# chargetime_v1.net
KiCad netlist of a schematic drawn in EAGLE
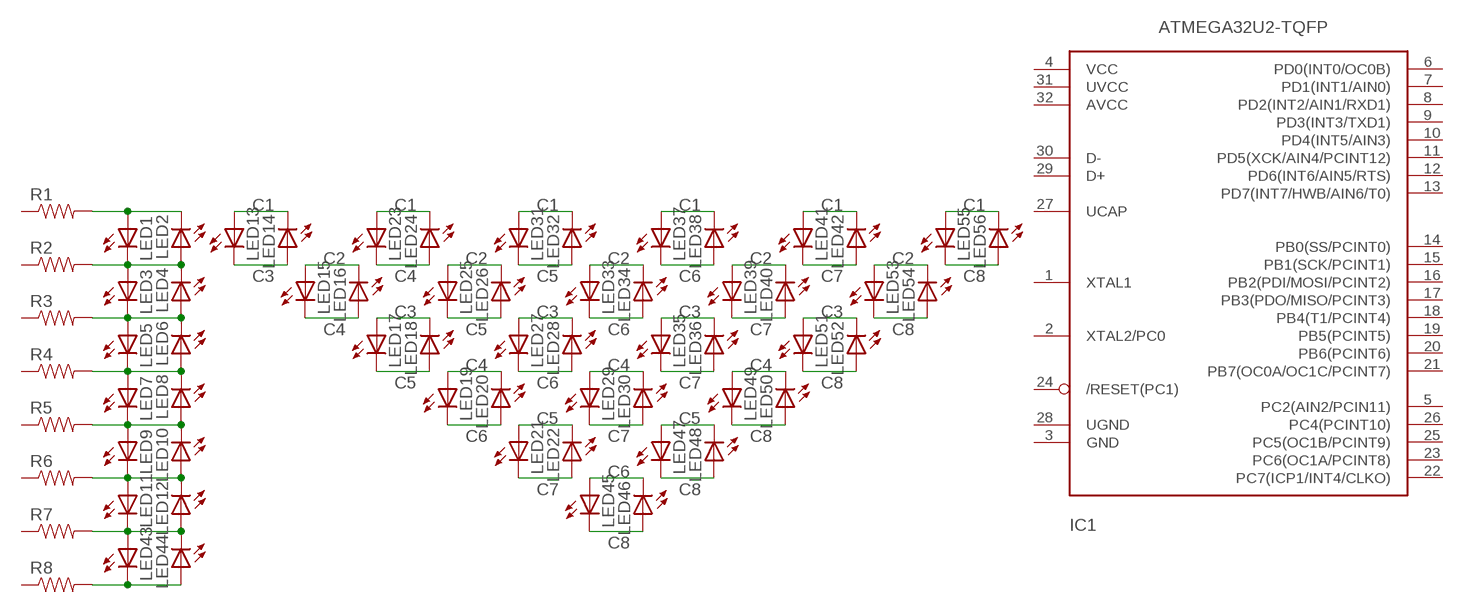
[diagram p0: schematic, sheet 1]

(export (version "E")
  (design (tool "Eeschema 10.0.6"))
  (components
    (comp (ref "IC1")
      (value "ATMEGA32U2-TQFP")
      (footprint "eagle-import:TQFP32-08")
      (libsource (lib "eagle-import") (part "ATMEGA32U2-TQFP"))
    )
    (comp (ref "LED1")
      (value "LEDCHIPLED_1206")
      (footprint "eagle-import:CHIPLED_1206")
      (libsource (lib "eagle-import") (part "LEDCHIPLED_1206"))
    )
    (comp (ref "LED2")
      (value "LEDCHIPLED_1206")
      (footprint "eagle-import:CHIPLED_1206")
      (libsource (lib "eagle-import") (part "LEDCHIPLED_1206"))
    )
    (comp (ref "LED3")
      (value "LEDCHIPLED_1206")
      (footprint "eagle-import:CHIPLED_1206")
      (libsource (lib "eagle-import") (part "LEDCHIPLED_1206"))
    )
    (comp (ref "LED4")
      (value "LEDCHIPLED_1206")
      (footprint "eagle-import:CHIPLED_1206")
      (libsource (lib "eagle-import") (part "LEDCHIPLED_1206"))
    )
    (comp (ref "LED5")
      (value "LEDCHIPLED_1206")
      (footprint "eagle-import:CHIPLED_1206")
      (libsource (lib "eagle-import") (part "LEDCHIPLED_1206"))
    )
    (comp (ref "LED6")
      (value "LEDCHIPLED_1206")
      (footprint "eagle-import:CHIPLED_1206")
      (libsource (lib "eagle-import") (part "LEDCHIPLED_1206"))
    )
    (comp (ref "LED7")
      (value "LEDCHIPLED_1206")
      (footprint "eagle-import:CHIPLED_1206")
      (libsource (lib "eagle-import") (part "LEDCHIPLED_1206"))
    )
    (comp (ref "LED8")
      (value "LEDCHIPLED_1206")
      (footprint "eagle-import:CHIPLED_1206")
      (libsource (lib "eagle-import") (part "LEDCHIPLED_1206"))
    )
    (comp (ref "LED9")
      (value "LEDCHIPLED_1206")
      (footprint "eagle-import:CHIPLED_1206")
      (libsource (lib "eagle-import") (part "LEDCHIPLED_1206"))
    )
    (comp (ref "LED10")
      (value "LEDCHIPLED_1206")
      (footprint "eagle-import:CHIPLED_1206")
      (libsource (lib "eagle-import") (part "LEDCHIPLED_1206"))
    )
    (comp (ref "LED11")
      (value "LEDCHIPLED_1206")
      (footprint "eagle-import:CHIPLED_1206")
      (libsource (lib "eagle-import") (part "LEDCHIPLED_1206"))
    )
    (comp (ref "LED12")
      (value "LEDCHIPLED_1206")
      (footprint "eagle-import:CHIPLED_1206")
      (libsource (lib "eagle-import") (part "LEDCHIPLED_1206"))
    )
    (comp (ref "LED13")
      (value "LEDCHIPLED_1206")
      (footprint "eagle-import:CHIPLED_1206")
      (libsource (lib "eagle-import") (part "LEDCHIPLED_1206"))
    )
    (comp (ref "LED14")
      (value "LEDCHIPLED_1206")
      (footprint "eagle-import:CHIPLED_1206")
      (libsource (lib "eagle-import") (part "LEDCHIPLED_1206"))
    )
    (comp (ref "LED15")
      (value "LEDCHIPLED_1206")
      (footprint "eagle-import:CHIPLED_1206")
      (libsource (lib "eagle-import") (part "LEDCHIPLED_1206"))
    )
    (comp (ref "LED16")
      (value "LEDCHIPLED_1206")
      (footprint "eagle-import:CHIPLED_1206")
      (libsource (lib "eagle-import") (part "LEDCHIPLED_1206"))
    )
    (comp (ref "LED17")
      (value "LEDCHIPLED_1206")
      (footprint "eagle-import:CHIPLED_1206")
      (libsource (lib "eagle-import") (part "LEDCHIPLED_1206"))
    )
    (comp (ref "LED18")
      (value "LEDCHIPLED_1206")
      (footprint "eagle-import:CHIPLED_1206")
      (libsource (lib "eagle-import") (part "LEDCHIPLED_1206"))
    )
    (comp (ref "LED19")
      (value "LEDCHIPLED_1206")
      (footprint "eagle-import:CHIPLED_1206")
      (libsource (lib "eagle-import") (part "LEDCHIPLED_1206"))
    )
    (comp (ref "LED20")
      (value "LEDCHIPLED_1206")
      (footprint "eagle-import:CHIPLED_1206")
      (libsource (lib "eagle-import") (part "LEDCHIPLED_1206"))
    )
    (comp (ref "LED21")
      (value "LEDCHIPLED_1206")
      (footprint "eagle-import:CHIPLED_1206")
      (libsource (lib "eagle-import") (part "LEDCHIPLED_1206"))
    )
    (comp (ref "LED22")
      (value "LEDCHIPLED_1206")
      (footprint "eagle-import:CHIPLED_1206")
      (libsource (lib "eagle-import") (part "LEDCHIPLED_1206"))
    )
    (comp (ref "LED23")
      (value "LEDCHIPLED_1206")
      (footprint "eagle-import:CHIPLED_1206")
      (libsource (lib "eagle-import") (part "LEDCHIPLED_1206"))
    )
    (comp (ref "LED24")
      (value "LEDCHIPLED_1206")
      (footprint "eagle-import:CHIPLED_1206")
      (libsource (lib "eagle-import") (part "LEDCHIPLED_1206"))
    )
    (comp (ref "LED25")
      (value "LEDCHIPLED_1206")
      (footprint "eagle-import:CHIPLED_1206")
      (libsource (lib "eagle-import") (part "LEDCHIPLED_1206"))
    )
    (comp (ref "LED26")
      (value "LEDCHIPLED_1206")
      (footprint "eagle-import:CHIPLED_1206")
      (libsource (lib "eagle-import") (part "LEDCHIPLED_1206"))
    )
    (comp (ref "LED27")
      (value "LEDCHIPLED_1206")
      (footprint "eagle-import:CHIPLED_1206")
      (libsource (lib "eagle-import") (part "LEDCHIPLED_1206"))
    )
    (comp (ref "LED28")
      (value "LEDCHIPLED_1206")
      (footprint "eagle-import:CHIPLED_1206")
      (libsource (lib "eagle-import") (part "LEDCHIPLED_1206"))
    )
    (comp (ref "LED29")
      (value "LEDCHIPLED_1206")
      (footprint "eagle-import:CHIPLED_1206")
      (libsource (lib "eagle-import") (part "LEDCHIPLED_1206"))
    )
    (comp (ref "LED30")
      (value "LEDCHIPLED_1206")
      (footprint "eagle-import:CHIPLED_1206")
      (libsource (lib "eagle-import") (part "LEDCHIPLED_1206"))
    )
    (comp (ref "LED31")
      (value "LEDCHIPLED_1206")
      (footprint "eagle-import:CHIPLED_1206")
      (libsource (lib "eagle-import") (part "LEDCHIPLED_1206"))
    )
    (comp (ref "LED32")
      (value "LEDCHIPLED_1206")
      (footprint "eagle-import:CHIPLED_1206")
      (libsource (lib "eagle-import") (part "LEDCHIPLED_1206"))
    )
    (comp (ref "LED33")
      (value "LEDCHIPLED_1206")
      (footprint "eagle-import:CHIPLED_1206")
      (libsource (lib "eagle-import") (part "LEDCHIPLED_1206"))
    )
    (comp (ref "LED34")
      (value "LEDCHIPLED_1206")
      (footprint "eagle-import:CHIPLED_1206")
      (libsource (lib "eagle-import") (part "LEDCHIPLED_1206"))
    )
    (comp (ref "LED35")
      (value "LEDCHIPLED_1206")
      (footprint "eagle-import:CHIPLED_1206")
      (libsource (lib "eagle-import") (part "LEDCHIPLED_1206"))
    )
    (comp (ref "LED36")
      (value "LEDCHIPLED_1206")
      (footprint "eagle-import:CHIPLED_1206")
      (libsource (lib "eagle-import") (part "LEDCHIPLED_1206"))
    )
    (comp (ref "LED37")
      (value "LEDCHIPLED_1206")
      (footprint "eagle-import:CHIPLED_1206")
      (libsource (lib "eagle-import") (part "LEDCHIPLED_1206"))
    )
    (comp (ref "LED38")
      (value "LEDCHIPLED_1206")
      (footprint "eagle-import:CHIPLED_1206")
      (libsource (lib "eagle-import") (part "LEDCHIPLED_1206"))
    )
    (comp (ref "LED39")
      (value "LEDCHIPLED_1206")
      (footprint "eagle-import:CHIPLED_1206")
      (libsource (lib "eagle-import") (part "LEDCHIPLED_1206"))
    )
    (comp (ref "LED40")
      (value "LEDCHIPLED_1206")
      (footprint "eagle-import:CHIPLED_1206")
      (libsource (lib "eagle-import") (part "LEDCHIPLED_1206"))
    )
    (comp (ref "LED41")
      (value "LEDCHIPLED_1206")
      (footprint "eagle-import:CHIPLED_1206")
      (libsource (lib "eagle-import") (part "LEDCHIPLED_1206"))
    )
    (comp (ref "LED42")
      (value "LEDCHIPLED_1206")
      (footprint "eagle-import:CHIPLED_1206")
      (libsource (lib "eagle-import") (part "LEDCHIPLED_1206"))
    )
    (comp (ref "LED43")
      (value "LEDCHIPLED_1206")
      (footprint "eagle-import:CHIPLED_1206")
      (libsource (lib "eagle-import") (part "LEDCHIPLED_1206"))
    )
    (comp (ref "LED44")
      (value "LEDCHIPLED_1206")
      (footprint "eagle-import:CHIPLED_1206")
      (libsource (lib "eagle-import") (part "LEDCHIPLED_1206"))
    )
    (comp (ref "LED45")
      (value "LEDCHIPLED_1206")
      (footprint "eagle-import:CHIPLED_1206")
      (libsource (lib "eagle-import") (part "LEDCHIPLED_1206"))
    )
    (comp (ref "LED46")
      (value "LEDCHIPLED_1206")
      (footprint "eagle-import:CHIPLED_1206")
      (libsource (lib "eagle-import") (part "LEDCHIPLED_1206"))
    )
    (comp (ref "LED47")
      (value "LEDCHIPLED_1206")
      (footprint "eagle-import:CHIPLED_1206")
      (libsource (lib "eagle-import") (part "LEDCHIPLED_1206"))
    )
    (comp (ref "LED48")
      (value "LEDCHIPLED_1206")
      (footprint "eagle-import:CHIPLED_1206")
      (libsource (lib "eagle-import") (part "LEDCHIPLED_1206"))
    )
    (comp (ref "LED49")
      (value "LEDCHIPLED_1206")
      (footprint "eagle-import:CHIPLED_1206")
      (libsource (lib "eagle-import") (part "LEDCHIPLED_1206"))
    )
    (comp (ref "LED50")
      (value "LEDCHIPLED_1206")
      (footprint "eagle-import:CHIPLED_1206")
      (libsource (lib "eagle-import") (part "LEDCHIPLED_1206"))
    )
    (comp (ref "LED51")
      (value "LEDCHIPLED_1206")
      (footprint "eagle-import:CHIPLED_1206")
      (libsource (lib "eagle-import") (part "LEDCHIPLED_1206"))
    )
    (comp (ref "LED52")
      (value "LEDCHIPLED_1206")
      (footprint "eagle-import:CHIPLED_1206")
      (libsource (lib "eagle-import") (part "LEDCHIPLED_1206"))
    )
    (comp (ref "LED53")
      (value "LEDCHIPLED_1206")
      (footprint "eagle-import:CHIPLED_1206")
      (libsource (lib "eagle-import") (part "LEDCHIPLED_1206"))
    )
    (comp (ref "LED54")
      (value "LEDCHIPLED_1206")
      (footprint "eagle-import:CHIPLED_1206")
      (libsource (lib "eagle-import") (part "LEDCHIPLED_1206"))
    )
    (comp (ref "LED55")
      (value "LEDCHIPLED_1206")
      (footprint "eagle-import:CHIPLED_1206")
      (libsource (lib "eagle-import") (part "LEDCHIPLED_1206"))
    )
    (comp (ref "LED56")
      (value "LEDCHIPLED_1206")
      (footprint "eagle-import:CHIPLED_1206")
      (libsource (lib "eagle-import") (part "LEDCHIPLED_1206"))
    )
    (comp (ref "R1")
      (value "RESISTOR1206")
      (footprint "eagle-import:1206")
      (libsource (lib "eagle-import") (part "RESISTOR1206"))
    )
    (comp (ref "R2")
      (value "RESISTOR1206")
      (footprint "eagle-import:1206")
      (libsource (lib "eagle-import") (part "RESISTOR1206"))
    )
    (comp (ref "R3")
      (value "RESISTOR1206")
      (footprint "eagle-import:1206")
      (libsource (lib "eagle-import") (part "RESISTOR1206"))
    )
    (comp (ref "R4")
      (value "RESISTOR1206")
      (footprint "eagle-import:1206")
      (libsource (lib "eagle-import") (part "RESISTOR1206"))
    )
    (comp (ref "R5")
      (value "RESISTOR1206")
      (footprint "eagle-import:1206")
      (libsource (lib "eagle-import") (part "RESISTOR1206"))
    )
    (comp (ref "R6")
      (value "RESISTOR1206")
      (footprint "eagle-import:1206")
      (libsource (lib "eagle-import") (part "RESISTOR1206"))
    )
    (comp (ref "R7")
      (value "RESISTOR1206")
      (footprint "eagle-import:1206")
      (libsource (lib "eagle-import") (part "RESISTOR1206"))
    )
    (comp (ref "R8")
      (value "RESISTOR1206")
      (footprint "eagle-import:1206")
      (libsource (lib "eagle-import") (part "RESISTOR1206"))
    )
  )
  (nets
    (net (code "1") (name "/C1") (class "Default")
      (node (ref "LED1") (pin "A") (pinfunction "A_A") (pintype "passive"))
      (node (ref "LED13") (pin "A") (pinfunction "A_A") (pintype "passive"))
      (node (ref "LED14") (pin "C") (pinfunction "C_C") (pintype "passive"))
      (node (ref "LED2") (pin "C") (pinfunction "C_C") (pintype "passive"))
      (node (ref "LED23") (pin "A") (pinfunction "A_A") (pintype "passive"))
      (node (ref "LED24") (pin "C") (pinfunction "C_C") (pintype "passive"))
      (node (ref "LED31") (pin "A") (pinfunction "A_A") (pintype "passive"))
      (node (ref "LED32") (pin "C") (pinfunction "C_C") (pintype "passive"))
      (node (ref "LED37") (pin "A") (pinfunction "A_A") (pintype "passive"))
      (node (ref "LED38") (pin "C") (pinfunction "C_C") (pintype "passive"))
      (node (ref "LED41") (pin "A") (pinfunction "A_A") (pintype "passive"))
      (node (ref "LED42") (pin "C") (pinfunction "C_C") (pintype "passive"))
      (node (ref "LED55") (pin "A") (pinfunction "A_A") (pintype "passive"))
      (node (ref "LED56") (pin "C") (pinfunction "C_C") (pintype "passive"))
      (node (ref "R1") (pin "2") (pinfunction "2_2") (pintype "passive"))
    )
    (net (code "2") (name "/C2") (class "Default")
      (node (ref "LED1") (pin "C") (pinfunction "C_C") (pintype "passive"))
      (node (ref "LED15") (pin "A") (pinfunction "A_A") (pintype "passive"))
      (node (ref "LED16") (pin "C") (pinfunction "C_C") (pintype "passive"))
      (node (ref "LED2") (pin "A") (pinfunction "A_A") (pintype "passive"))
      (node (ref "LED25") (pin "A") (pinfunction "A_A") (pintype "passive"))
      (node (ref "LED26") (pin "C") (pinfunction "C_C") (pintype "passive"))
      (node (ref "LED3") (pin "A") (pinfunction "A_A") (pintype "passive"))
      (node (ref "LED33") (pin "A") (pinfunction "A_A") (pintype "passive"))
      (node (ref "LED34") (pin "C") (pinfunction "C_C") (pintype "passive"))
      (node (ref "LED39") (pin "A") (pinfunction "A_A") (pintype "passive"))
      (node (ref "LED4") (pin "C") (pinfunction "C_C") (pintype "passive"))
      (node (ref "LED40") (pin "C") (pinfunction "C_C") (pintype "passive"))
      (node (ref "LED53") (pin "A") (pinfunction "A_A") (pintype "passive"))
      (node (ref "LED54") (pin "C") (pinfunction "C_C") (pintype "passive"))
      (node (ref "R2") (pin "2") (pinfunction "2_2") (pintype "passive"))
    )
    (net (code "3") (name "/C3") (class "Default")
      (node (ref "LED13") (pin "C") (pinfunction "C_C") (pintype "passive"))
      (node (ref "LED14") (pin "A") (pinfunction "A_A") (pintype "passive"))
      (node (ref "LED17") (pin "A") (pinfunction "A_A") (pintype "passive"))
      (node (ref "LED18") (pin "C") (pinfunction "C_C") (pintype "passive"))
      (node (ref "LED27") (pin "A") (pinfunction "A_A") (pintype "passive"))
      (node (ref "LED28") (pin "C") (pinfunction "C_C") (pintype "passive"))
      (node (ref "LED3") (pin "C") (pinfunction "C_C") (pintype "passive"))
      (node (ref "LED35") (pin "A") (pinfunction "A_A") (pintype "passive"))
      (node (ref "LED36") (pin "C") (pinfunction "C_C") (pintype "passive"))
      (node (ref "LED4") (pin "A") (pinfunction "A_A") (pintype "passive"))
      (node (ref "LED5") (pin "A") (pinfunction "A_A") (pintype "passive"))
      (node (ref "LED51") (pin "A") (pinfunction "A_A") (pintype "passive"))
      (node (ref "LED52") (pin "C") (pinfunction "C_C") (pintype "passive"))
      (node (ref "LED6") (pin "C") (pinfunction "C_C") (pintype "passive"))
      (node (ref "R3") (pin "2") (pinfunction "2_2") (pintype "passive"))
    )
    (net (code "4") (name "/C4") (class "Default")
      (node (ref "LED15") (pin "C") (pinfunction "C_C") (pintype "passive"))
      (node (ref "LED16") (pin "A") (pinfunction "A_A") (pintype "passive"))
      (node (ref "LED19") (pin "A") (pinfunction "A_A") (pintype "passive"))
      (node (ref "LED20") (pin "C") (pinfunction "C_C") (pintype "passive"))
      (node (ref "LED23") (pin "C") (pinfunction "C_C") (pintype "passive"))
      (node (ref "LED24") (pin "A") (pinfunction "A_A") (pintype "passive"))
      (node (ref "LED29") (pin "A") (pinfunction "A_A") (pintype "passive"))
      (node (ref "LED30") (pin "C") (pinfunction "C_C") (pintype "passive"))
      (node (ref "LED49") (pin "A") (pinfunction "A_A") (pintype "passive"))
      (node (ref "LED5") (pin "C") (pinfunction "C_C") (pintype "passive"))
      (node (ref "LED50") (pin "C") (pinfunction "C_C") (pintype "passive"))
      (node (ref "LED6") (pin "A") (pinfunction "A_A") (pintype "passive"))
      (node (ref "LED7") (pin "A") (pinfunction "A_A") (pintype "passive"))
      (node (ref "LED8") (pin "C") (pinfunction "C_C") (pintype "passive"))
      (node (ref "R4") (pin "2") (pinfunction "2_2") (pintype "passive"))
    )
    (net (code "5") (name "/C5") (class "Default")
      (node (ref "LED10") (pin "C") (pinfunction "C_C") (pintype "passive"))
      (node (ref "LED17") (pin "C") (pinfunction "C_C") (pintype "passive"))
      (node (ref "LED18") (pin "A") (pinfunction "A_A") (pintype "passive"))
      (node (ref "LED21") (pin "A") (pinfunction "A_A") (pintype "passive"))
      (node (ref "LED22") (pin "C") (pinfunction "C_C") (pintype "passive"))
      (node (ref "LED25") (pin "C") (pinfunction "C_C") (pintype "passive"))
      (node (ref "LED26") (pin "A") (pinfunction "A_A") (pintype "passive"))
      (node (ref "LED31") (pin "C") (pinfunction "C_C") (pintype "passive"))
      (node (ref "LED32") (pin "A") (pinfunction "A_A") (pintype "passive"))
      (node (ref "LED47") (pin "A") (pinfunction "A_A") (pintype "passive"))
      (node (ref "LED48") (pin "C") (pinfunction "C_C") (pintype "passive"))
      (node (ref "LED7") (pin "C") (pinfunction "C_C") (pintype "passive"))
      (node (ref "LED8") (pin "A") (pinfunction "A_A") (pintype "passive"))
      (node (ref "LED9") (pin "A") (pinfunction "A_A") (pintype "passive"))
      (node (ref "R5") (pin "2") (pinfunction "2_2") (pintype "passive"))
    )
    (net (code "6") (name "/C6") (class "Default")
      (node (ref "LED10") (pin "A") (pinfunction "A_A") (pintype "passive"))
      (node (ref "LED11") (pin "A") (pinfunction "A_A") (pintype "passive"))
      (node (ref "LED12") (pin "C") (pinfunction "C_C") (pintype "passive"))
      (node (ref "LED19") (pin "C") (pinfunction "C_C") (pintype "passive"))
      (node (ref "LED20") (pin "A") (pinfunction "A_A") (pintype "passive"))
      (node (ref "LED27") (pin "C") (pinfunction "C_C") (pintype "passive"))
      (node (ref "LED28") (pin "A") (pinfunction "A_A") (pintype "passive"))
      (node (ref "LED33") (pin "C") (pinfunction "C_C") (pintype "passive"))
      (node (ref "LED34") (pin "A") (pinfunction "A_A") (pintype "passive"))
      (node (ref "LED37") (pin "C") (pinfunction "C_C") (pintype "passive"))
      (node (ref "LED38") (pin "A") (pinfunction "A_A") (pintype "passive"))
      (node (ref "LED45") (pin "A") (pinfunction "A_A") (pintype "passive"))
      (node (ref "LED46") (pin "C") (pinfunction "C_C") (pintype "passive"))
      (node (ref "LED9") (pin "C") (pinfunction "C_C") (pintype "passive"))
      (node (ref "R6") (pin "2") (pinfunction "2_2") (pintype "passive"))
    )
    (net (code "7") (name "/C7") (class "Default")
      (node (ref "LED11") (pin "C") (pinfunction "C_C") (pintype "passive"))
      (node (ref "LED12") (pin "A") (pinfunction "A_A") (pintype "passive"))
      (node (ref "LED21") (pin "C") (pinfunction "C_C") (pintype "passive"))
      (node (ref "LED22") (pin "A") (pinfunction "A_A") (pintype "passive"))
      (node (ref "LED29") (pin "C") (pinfunction "C_C") (pintype "passive"))
      (node (ref "LED30") (pin "A") (pinfunction "A_A") (pintype "passive"))
      (node (ref "LED35") (pin "C") (pinfunction "C_C") (pintype "passive"))
      (node (ref "LED36") (pin "A") (pinfunction "A_A") (pintype "passive"))
      (node (ref "LED39") (pin "C") (pinfunction "C_C") (pintype "passive"))
      (node (ref "LED40") (pin "A") (pinfunction "A_A") (pintype "passive"))
      (node (ref "LED41") (pin "C") (pinfunction "C_C") (pintype "passive"))
      (node (ref "LED42") (pin "A") (pinfunction "A_A") (pintype "passive"))
      (node (ref "LED43") (pin "A") (pinfunction "A_A") (pintype "passive"))
      (node (ref "LED44") (pin "C") (pinfunction "C_C") (pintype "passive"))
      (node (ref "R7") (pin "2") (pinfunction "2_2") (pintype "passive"))
    )
    (net (code "8") (name "/C8") (class "Default")
      (node (ref "LED43") (pin "C") (pinfunction "C_C") (pintype "passive"))
      (node (ref "LED44") (pin "A") (pinfunction "A_A") (pintype "passive"))
      (node (ref "LED45") (pin "C") (pinfunction "C_C") (pintype "passive"))
      (node (ref "LED46") (pin "A") (pinfunction "A_A") (pintype "passive"))
      (node (ref "LED47") (pin "C") (pinfunction "C_C") (pintype "passive"))
      (node (ref "LED48") (pin "A") (pinfunction "A_A") (pintype "passive"))
      (node (ref "LED49") (pin "C") (pinfunction "C_C") (pintype "passive"))
      (node (ref "LED50") (pin "A") (pinfunction "A_A") (pintype "passive"))
      (node (ref "LED51") (pin "C") (pinfunction "C_C") (pintype "passive"))
      (node (ref "LED52") (pin "A") (pinfunction "A_A") (pintype "passive"))
      (node (ref "LED53") (pin "C") (pinfunction "C_C") (pintype "passive"))
      (node (ref "LED54") (pin "A") (pinfunction "A_A") (pintype "passive"))
      (node (ref "LED55") (pin "C") (pinfunction "C_C") (pintype "passive"))
      (node (ref "LED56") (pin "A") (pinfunction "A_A") (pintype "passive"))
      (node (ref "R8") (pin "2") (pinfunction "2_2") (pintype "passive"))
    )
    (net (code "9") (name "unconnected-(IC1-AVCC-Pad32)") (class "Default")
      (node (ref "IC1") (pin "32") (pinfunction "AVCC_32") (pintype "bidirectional"))
    )
    (net (code "10") (name "unconnected-(IC1-D+-Pad29)") (class "Default")
      (node (ref "IC1") (pin "29") (pinfunction "D+_29") (pintype "bidirectional"))
    )
    (net (code "11") (name "unconnected-(IC1-D--Pad30)") (class "Default")
      (node (ref "IC1") (pin "30") (pinfunction "D-_30") (pintype "bidirectional"))
    )
    (net (code "12") (name "unconnected-(IC1-GND-Pad3)") (class "Default")
      (node (ref "IC1") (pin "3") (pinfunction "GND_3") (pintype "bidirectional"))
    )
    (net (code "13") (name "unconnected-(IC1-PB0(SS{slash}PCINT0)-Pad14)") (class "Default")
      (node (ref "IC1") (pin "14") (pinfunction "PB0(SS/PCINT0)_14") (pintype "bidirectional"))
    )
    (net (code "14") (name "unconnected-(IC1-PB1(SCK{slash}PCINT1)-Pad15)") (class "Default")
      (node (ref "IC1") (pin "15") (pinfunction "PB1(SCK/PCINT1)_15") (pintype "bidirectional"))
    )
    (net (code "15") (name "unconnected-(IC1-PB2(PDI{slash}MOSI{slash}PCINT2)-Pad16)") (class "Default")
      (node (ref "IC1") (pin "16") (pinfunction "PB2(PDI/MOSI/PCINT2)_16") (pintype "bidirectional"))
    )
    (net (code "16") (name "unconnected-(IC1-PB3(PDO{slash}MISO{slash}PCINT3)-Pad17)") (class "Default")
      (node (ref "IC1") (pin "17") (pinfunction "PB3(PDO/MISO/PCINT3)_17") (pintype "bidirectional"))
    )
    (net (code "17") (name "unconnected-(IC1-PB4(T1{slash}PCINT4)-Pad18)") (class "Default")
      (node (ref "IC1") (pin "18") (pinfunction "PB4(T1/PCINT4)_18") (pintype "bidirectional"))
    )
    (net (code "18") (name "unconnected-(IC1-PB5(PCINT5)-Pad19)") (class "Default")
      (node (ref "IC1") (pin "19") (pinfunction "PB5(PCINT5)_19") (pintype "bidirectional"))
    )
    (net (code "19") (name "unconnected-(IC1-PB6(PCINT6)-Pad20)") (class "Default")
      (node (ref "IC1") (pin "20") (pinfunction "PB6(PCINT6)_20") (pintype "bidirectional"))
    )
    (net (code "20") (name "unconnected-(IC1-PB7(OC0A{slash}OC1C{slash}PCINT7)-Pad21)") (class "Default")
      (node (ref "IC1") (pin "21") (pinfunction "PB7(OC0A/OC1C/PCINT7)_21") (pintype "bidirectional"))
    )
    (net (code "21") (name "unconnected-(IC1-PC2(AIN2{slash}PCIN11)-Pad5)") (class "Default")
      (node (ref "IC1") (pin "5") (pinfunction "PC2(AIN2/PCIN11)_5") (pintype "bidirectional"))
    )
    (net (code "22") (name "unconnected-(IC1-PC4(PCINT10)-Pad26)") (class "Default")
      (node (ref "IC1") (pin "26") (pinfunction "PC4(PCINT10)_26") (pintype "bidirectional"))
    )
    (net (code "23") (name "unconnected-(IC1-PC5(OC1B{slash}PCINT9)-Pad25)") (class "Default")
      (node (ref "IC1") (pin "25") (pinfunction "PC5(OC1B/PCINT9)_25") (pintype "bidirectional"))
    )
    (net (code "24") (name "unconnected-(IC1-PC6(OC1A{slash}PCINT8)-Pad23)") (class "Default")
      (node (ref "IC1") (pin "23") (pinfunction "PC6(OC1A/PCINT8)_23") (pintype "bidirectional"))
    )
    (net (code "25") (name "unconnected-(IC1-PC7(ICP1{slash}INT4{slash}CLKO)-Pad22)") (class "Default")
      (node (ref "IC1") (pin "22") (pinfunction "PC7(ICP1/INT4/CLKO)_22") (pintype "bidirectional"))
    )
    (net (code "26") (name "unconnected-(IC1-PD0(INT0{slash}OC0B)-Pad6)") (class "Default")
      (node (ref "IC1") (pin "6") (pinfunction "PD0(INT0/OC0B)_6") (pintype "bidirectional"))
    )
    (net (code "27") (name "unconnected-(IC1-PD1(INT1{slash}AIN0)-Pad7)") (class "Default")
      (node (ref "IC1") (pin "7") (pinfunction "PD1(INT1/AIN0)_7") (pintype "bidirectional"))
    )
    (net (code "28") (name "unconnected-(IC1-PD2(INT2{slash}AIN1{slash}RXD1)-Pad8)") (class "Default")
      (node (ref "IC1") (pin "8") (pinfunction "PD2(INT2/AIN1/RXD1)_8") (pintype "bidirectional"))
    )
    (net (code "29") (name "unconnected-(IC1-PD3(INT3{slash}TXD1)-Pad9)") (class "Default")
      (node (ref "IC1") (pin "9") (pinfunction "PD3(INT3/TXD1)_9") (pintype "bidirectional"))
    )
    (net (code "30") (name "unconnected-(IC1-PD4(INT5{slash}AIN3)-Pad10)") (class "Default")
      (node (ref "IC1") (pin "10") (pinfunction "PD4(INT5/AIN3)_10") (pintype "bidirectional"))
    )
    (net (code "31") (name "unconnected-(IC1-PD5(XCK{slash}AIN4{slash}PCINT12)-Pad11)") (class "Default")
      (node (ref "IC1") (pin "11") (pinfunction "PD5(XCK/AIN4/PCINT12)_11") (pintype "bidirectional"))
    )
    (net (code "32") (name "unconnected-(IC1-PD6(INT6{slash}AIN5{slash}RTS)-Pad12)") (class "Default")
      (node (ref "IC1") (pin "12") (pinfunction "PD6(INT6/AIN5/RTS)_12") (pintype "bidirectional"))
    )
    (net (code "33") (name "unconnected-(IC1-PD7(INT7{slash}HWB{slash}AIN6{slash}T0)-Pad13)") (class "Default")
      (node (ref "IC1") (pin "13") (pinfunction "PD7(INT7/HWB/AIN6/T0)_13") (pintype "bidirectional"))
    )
    (net (code "34") (name "unconnected-(IC1-UCAP-Pad27)") (class "Default")
      (node (ref "IC1") (pin "27") (pinfunction "UCAP_27") (pintype "bidirectional"))
    )
    (net (code "35") (name "unconnected-(IC1-UGND-Pad28)") (class "Default")
      (node (ref "IC1") (pin "28") (pinfunction "UGND_28") (pintype "bidirectional"))
    )
    (net (code "36") (name "unconnected-(IC1-UVCC-Pad31)") (class "Default")
      (node (ref "IC1") (pin "31") (pinfunction "UVCC_31") (pintype "bidirectional"))
    )
    (net (code "37") (name "unconnected-(IC1-VCC-Pad4)") (class "Default")
      (node (ref "IC1") (pin "4") (pinfunction "VCC_4") (pintype "bidirectional"))
    )
    (net (code "38") (name "unconnected-(IC1-XTAL1-Pad1)") (class "Default")
      (node (ref "IC1") (pin "1") (pinfunction "XTAL1_1") (pintype "bidirectional"))
    )
    (net (code "39") (name "unconnected-(IC1-XTAL2{slash}PC0-Pad2)") (class "Default")
      (node (ref "IC1") (pin "2") (pinfunction "XTAL2/PC0_2") (pintype "bidirectional"))
    )
    (net (code "40") (name "unconnected-(IC1-{slash}RESET(PC1)-Pad24)") (class "Default")
      (node (ref "IC1") (pin "24") (pinfunction "/RESET(PC1)_24") (pintype "bidirectional"))
    )
    (net (code "41") (name "unconnected-(R1-Pad1)") (class "Default")
      (node (ref "R1") (pin "1") (pinfunction "1_1") (pintype "passive"))
    )
    (net (code "42") (name "unconnected-(R2-Pad1)") (class "Default")
      (node (ref "R2") (pin "1") (pinfunction "1_1") (pintype "passive"))
    )
    (net (code "43") (name "unconnected-(R3-Pad1)") (class "Default")
      (node (ref "R3") (pin "1") (pinfunction "1_1") (pintype "passive"))
    )
    (net (code "44") (name "unconnected-(R4-Pad1)") (class "Default")
      (node (ref "R4") (pin "1") (pinfunction "1_1") (pintype "passive"))
    )
    (net (code "45") (name "unconnected-(R5-Pad1)") (class "Default")
      (node (ref "R5") (pin "1") (pinfunction "1_1") (pintype "passive"))
    )
    (net (code "46") (name "unconnected-(R6-Pad1)") (class "Default")
      (node (ref "R6") (pin "1") (pinfunction "1_1") (pintype "passive"))
    )
    (net (code "47") (name "unconnected-(R7-Pad1)") (class "Default")
      (node (ref "R7") (pin "1") (pinfunction "1_1") (pintype "passive"))
    )
    (net (code "48") (name "unconnected-(R8-Pad1)") (class "Default")
      (node (ref "R8") (pin "1") (pinfunction "1_1") (pintype "passive"))
    )
  )
)
